# transmitter_with_KS0108_LCD.net
KiCad netlist of a schematic drawn in EAGLE
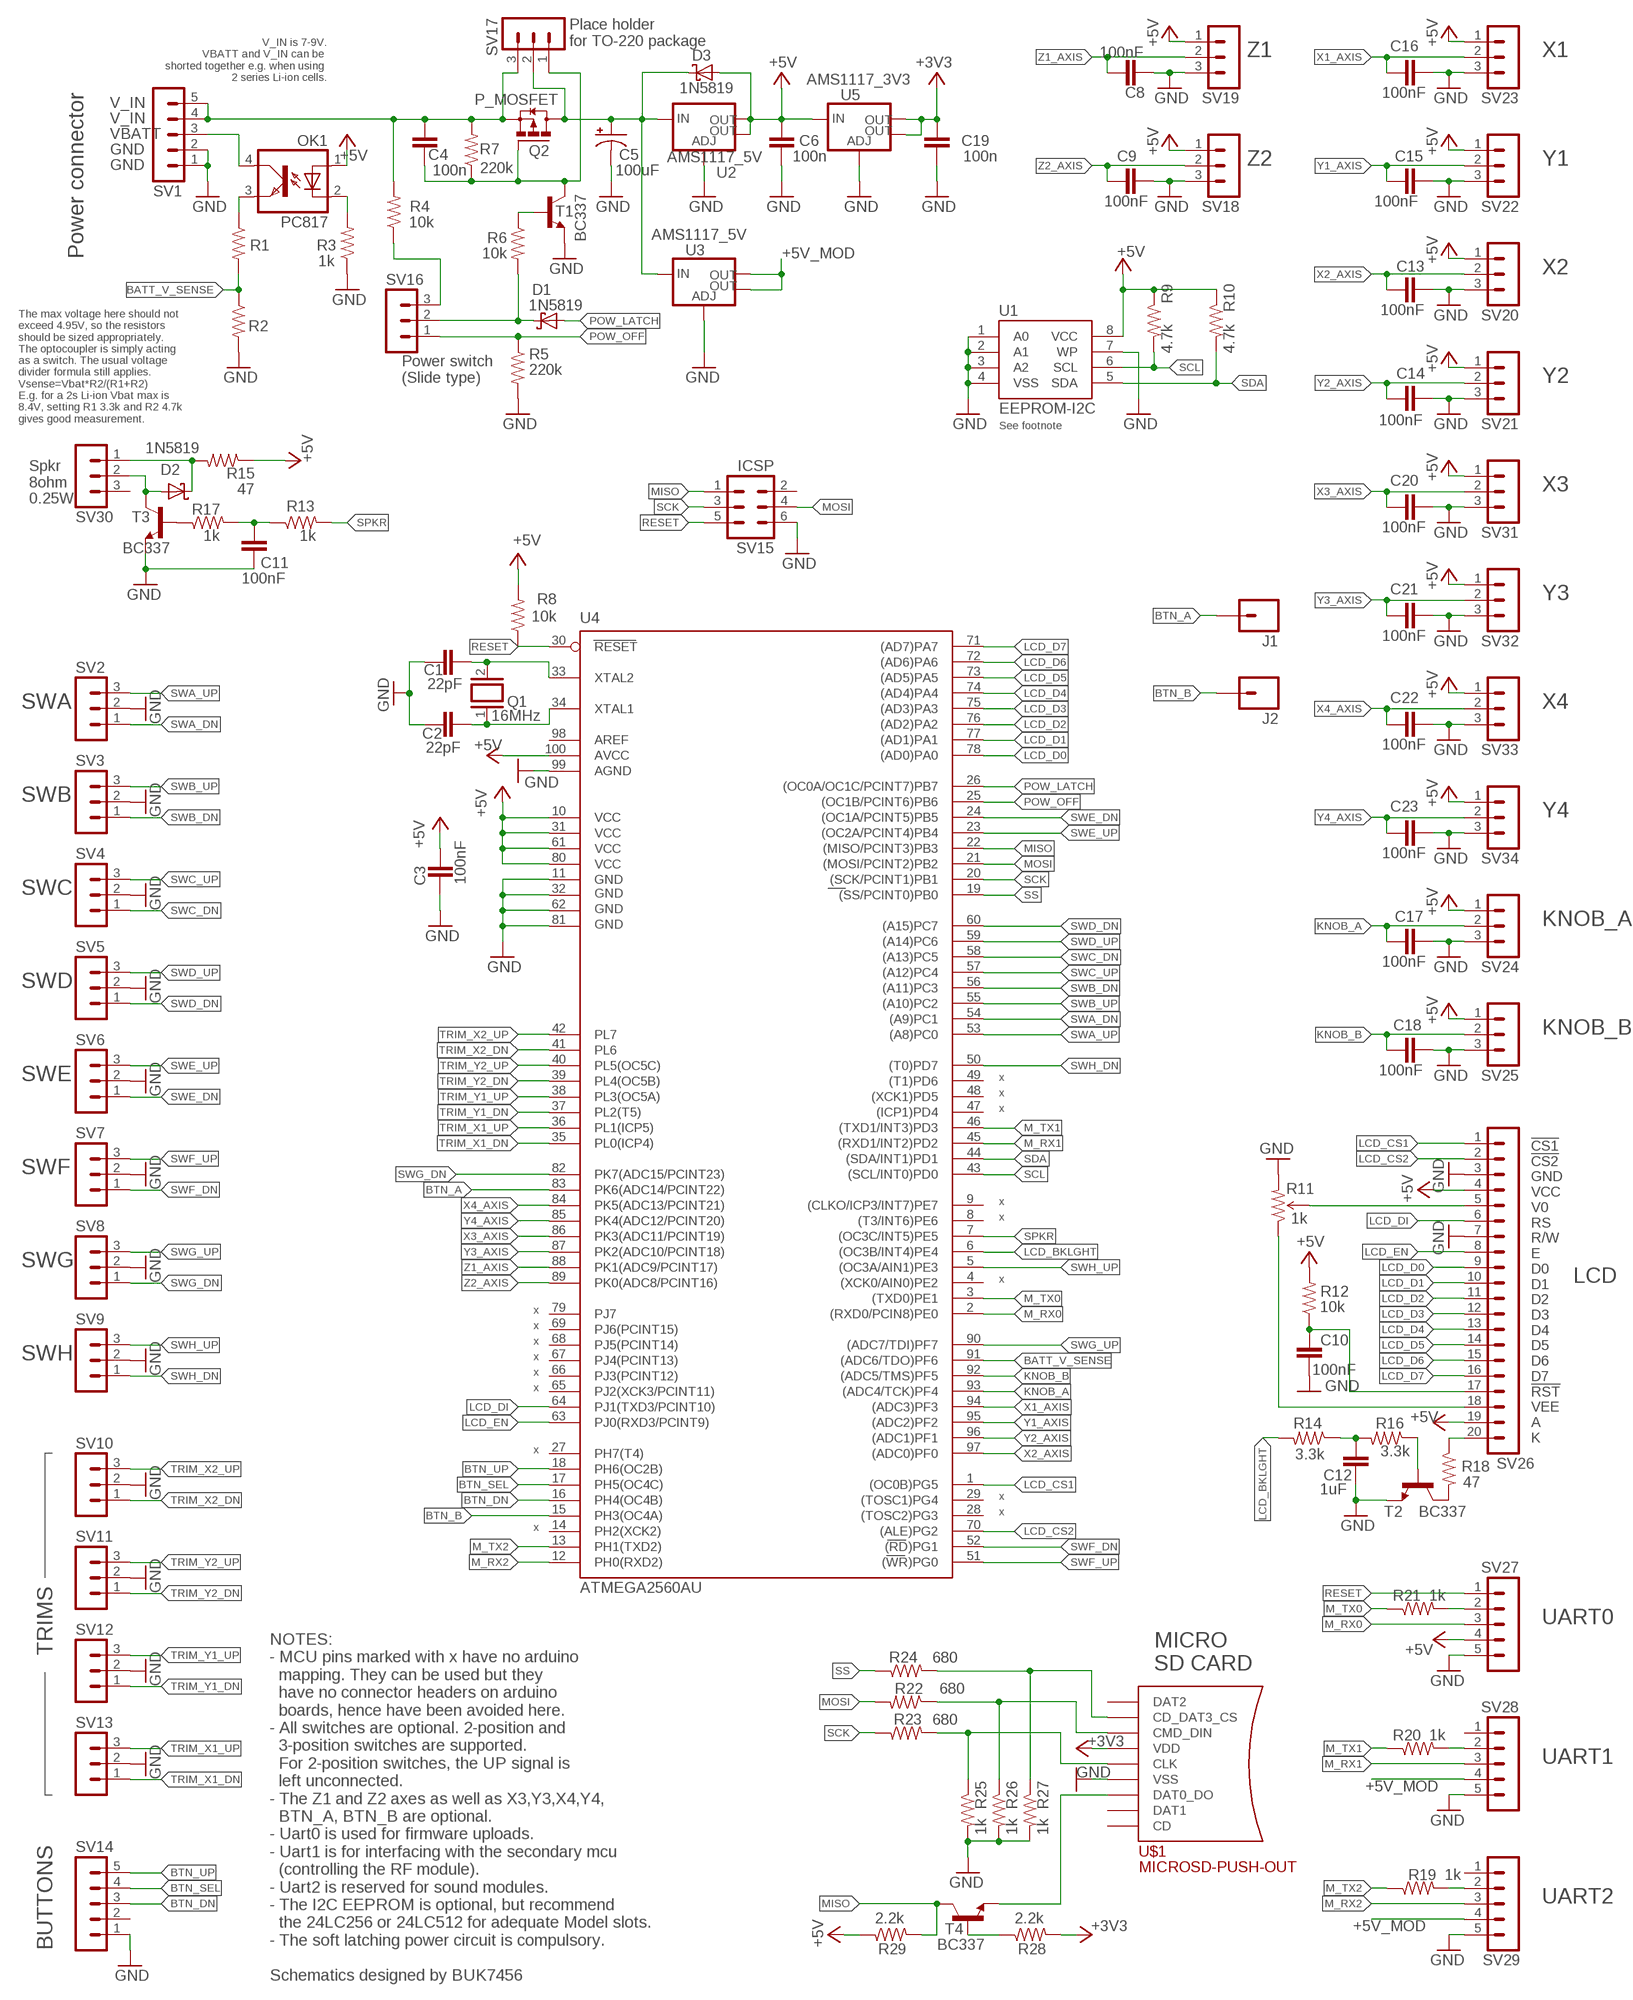
[diagram p0: schematic, sheet 1]

(export (version "E")
  (design (tool "Eeschema 10.0.6"))
  (components
    (comp (ref "C1")
      (value "22pF")
      (footprint "eagle-import:C050-024X044")
      (libsource (lib "eagle-import") (part "C-EU050-024X044"))
    )
    (comp (ref "C2")
      (value "22pF")
      (footprint "eagle-import:C050-024X044")
      (libsource (lib "eagle-import") (part "C-EU050-024X044"))
    )
    (comp (ref "C3")
      (value "100nF")
      (footprint "eagle-import:C050-024X044")
      (libsource (lib "eagle-import") (part "C-EU050-024X044"))
    )
    (comp (ref "C4")
      (value "100n")
      (footprint "eagle-import:C050-024X044")
      (libsource (lib "eagle-import") (part "C-EU050-024X044"))
    )
    (comp (ref "C5")
      (value "100uF")
      (footprint "eagle-import:E2,5-6E")
      (libsource (lib "eagle-import") (part "CPOL-USE2,5-6E"))
    )
    (comp (ref "C6")
      (value "100n")
      (footprint "eagle-import:C050-024X044")
      (libsource (lib "eagle-import") (part "C-EU050-024X044"))
    )
    (comp (ref "C8")
      (value "100nF")
      (footprint "eagle-import:C050-024X044")
      (libsource (lib "eagle-import") (part "C-EU050-024X044"))
    )
    (comp (ref "C9")
      (value "100nF")
      (footprint "eagle-import:C050-024X044")
      (libsource (lib "eagle-import") (part "C-EU050-024X044"))
    )
    (comp (ref "C10")
      (value "100nF")
      (footprint "eagle-import:C050-024X044")
      (libsource (lib "eagle-import") (part "C-EU050-024X044"))
    )
    (comp (ref "C11")
      (value "100nF")
      (footprint "eagle-import:C050-024X044")
      (libsource (lib "eagle-import") (part "C-EU050-024X044"))
    )
    (comp (ref "C12")
      (value "1uF")
      (footprint "eagle-import:C050-024X044")
      (libsource (lib "eagle-import") (part "C-EU050-024X044"))
    )
    (comp (ref "C13")
      (value "100nF")
      (footprint "eagle-import:C050-024X044")
      (libsource (lib "eagle-import") (part "C-EU050-024X044"))
    )
    (comp (ref "C14")
      (value "100nF")
      (footprint "eagle-import:C050-024X044")
      (libsource (lib "eagle-import") (part "C-EU050-024X044"))
    )
    (comp (ref "C15")
      (value "100nF")
      (footprint "eagle-import:C050-024X044")
      (libsource (lib "eagle-import") (part "C-EU050-024X044"))
    )
    (comp (ref "C16")
      (value "100nF")
      (footprint "eagle-import:C050-024X044")
      (libsource (lib "eagle-import") (part "C-EU050-024X044"))
    )
    (comp (ref "C17")
      (value "100nF")
      (footprint "eagle-import:C050-024X044")
      (libsource (lib "eagle-import") (part "C-EU050-024X044"))
    )
    (comp (ref "C18")
      (value "100nF")
      (footprint "eagle-import:C050-024X044")
      (libsource (lib "eagle-import") (part "C-EU050-024X044"))
    )
    (comp (ref "C19")
      (value "100n")
      (footprint "eagle-import:C050-024X044")
      (libsource (lib "eagle-import") (part "C-EU050-024X044"))
    )
    (comp (ref "C20")
      (value "100nF")
      (footprint "eagle-import:C050-024X044")
      (libsource (lib "eagle-import") (part "C-EU050-024X044"))
    )
    (comp (ref "C21")
      (value "100nF")
      (footprint "eagle-import:C050-024X044")
      (libsource (lib "eagle-import") (part "C-EU050-024X044"))
    )
    (comp (ref "C22")
      (value "100nF")
      (footprint "eagle-import:C050-024X044")
      (libsource (lib "eagle-import") (part "C-EU050-024X044"))
    )
    (comp (ref "C23")
      (value "100nF")
      (footprint "eagle-import:C050-024X044")
      (libsource (lib "eagle-import") (part "C-EU050-024X044"))
    )
    (comp (ref "D1")
      (value "1N5819")
      (footprint "eagle-import:DO41-7.6")
      (libsource (lib "eagle-import") (part "1N5817-B"))
    )
    (comp (ref "D2")
      (value "1N5819")
      (footprint "eagle-import:DO41-7.6")
      (libsource (lib "eagle-import") (part "1N5817-B"))
    )
    (comp (ref "D3")
      (value "1N5819")
      (footprint "eagle-import:DO41-7.6")
      (libsource (lib "eagle-import") (part "1N5817-B"))
    )
    (comp (ref "J1")
      (value "M01PTH_LONGPAD")
      (footprint "eagle-import:1X01_LONGPAD")
      (libsource (lib "eagle-import") (part "M01PTH_LONGPAD"))
    )
    (comp (ref "J2")
      (value "M01PTH_LONGPAD")
      (footprint "eagle-import:1X01_LONGPAD")
      (libsource (lib "eagle-import") (part "M01PTH_LONGPAD"))
    )
    (comp (ref "OK1")
      (value "PC817")
      (footprint "eagle-import:DIL04")
      (fields (field (name "MPN") "PC817X4J000F"))
      (libsource (lib "eagle-import") (part "PC817"))
    )
    (comp (ref "Q1")
      (value "16MHz")
      (footprint "eagle-import:QS")
      (libsource (lib "eagle-import") (part "XTAL/S"))
    )
    (comp (ref "Q2")
      (value "P_MOSFET")
      (footprint "eagle-import:SUPER-SOT3")
      (libsource (lib "eagle-import") (part "FDN360P"))
    )
    (comp (ref "R1")
      (value "1k")
      (footprint "eagle-import:0204_5")
      (libsource (lib "eagle-import") (part "R-US_0204/5"))
    )
    (comp (ref "R2")
      (value "1k")
      (footprint "eagle-import:0204_5")
      (libsource (lib "eagle-import") (part "R-US_0204/5"))
    )
    (comp (ref "R3")
      (value "1k")
      (footprint "eagle-import:0204_5")
      (libsource (lib "eagle-import") (part "R-US_0204/5"))
    )
    (comp (ref "R4")
      (value "10k")
      (footprint "eagle-import:0204_5")
      (libsource (lib "eagle-import") (part "R-US_0204/5"))
    )
    (comp (ref "R5")
      (value "220k")
      (footprint "eagle-import:0204_5")
      (libsource (lib "eagle-import") (part "R-US_0204/5"))
    )
    (comp (ref "R6")
      (value "10k")
      (footprint "eagle-import:0204_5")
      (libsource (lib "eagle-import") (part "R-US_0204/5"))
    )
    (comp (ref "R7")
      (value "220k")
      (footprint "eagle-import:0204_5")
      (libsource (lib "eagle-import") (part "R-US_0204/5"))
    )
    (comp (ref "R8")
      (value "10k")
      (footprint "eagle-import:0204_5")
      (libsource (lib "eagle-import") (part "R-US_0204/5"))
    )
    (comp (ref "R9")
      (value "4.7k")
      (footprint "eagle-import:0204_5")
      (libsource (lib "eagle-import") (part "R-US_0204/5"))
    )
    (comp (ref "R10")
      (value "4.7k")
      (footprint "eagle-import:0204_5")
      (libsource (lib "eagle-import") (part "R-US_0204/5"))
    )
    (comp (ref "R11")
      (value "1k")
      (footprint "eagle-import:TRIM_POT_PTH")
      (libsource (lib "eagle-import") (part "TRIMPOTPTH"))
    )
    (comp (ref "R12")
      (value "10k")
      (footprint "eagle-import:0204_5")
      (libsource (lib "eagle-import") (part "resistor_R-US_0204/5"))
    )
    (comp (ref "R13")
      (value "1k")
      (footprint "eagle-import:0204_5")
      (libsource (lib "eagle-import") (part "R-US_0204/5"))
    )
    (comp (ref "R14")
      (value "3.3k")
      (footprint "eagle-import:0204_5")
      (libsource (lib "eagle-import") (part "R-US_0204/5"))
    )
    (comp (ref "R15")
      (value "47")
      (footprint "eagle-import:0204_5")
      (libsource (lib "eagle-import") (part "R-US_0204/5"))
    )
    (comp (ref "R16")
      (value "3.3k")
      (footprint "eagle-import:0204_5")
      (libsource (lib "eagle-import") (part "R-US_0204/5"))
    )
    (comp (ref "R17")
      (value "1k")
      (footprint "eagle-import:0204_5")
      (libsource (lib "eagle-import") (part "R-US_0204/5"))
    )
    (comp (ref "R18")
      (value "47")
      (footprint "eagle-import:0204_5")
      (libsource (lib "eagle-import") (part "R-US_0204/5"))
    )
    (comp (ref "R19")
      (value "1k")
      (footprint "eagle-import:0204_5")
      (libsource (lib "eagle-import") (part "R-US_0204/5"))
    )
    (comp (ref "R20")
      (value "1k")
      (footprint "eagle-import:0204_5")
      (libsource (lib "eagle-import") (part "R-US_0204/5"))
    )
    (comp (ref "R21")
      (value "1k")
      (footprint "eagle-import:0204_5")
      (libsource (lib "eagle-import") (part "R-US_0204/5"))
    )
    (comp (ref "R22")
      (value "680")
      (footprint "eagle-import:0204_5")
      (libsource (lib "eagle-import") (part "R-US_0204/5"))
    )
    (comp (ref "R23")
      (value "680")
      (footprint "eagle-import:0204_5")
      (libsource (lib "eagle-import") (part "R-US_0204/5"))
    )
    (comp (ref "R24")
      (value "680")
      (footprint "eagle-import:0204_5")
      (libsource (lib "eagle-import") (part "R-US_0204/5"))
    )
    (comp (ref "R25")
      (value "1k")
      (footprint "eagle-import:0204_5")
      (libsource (lib "eagle-import") (part "R-US_0204/5"))
    )
    (comp (ref "R26")
      (value "1k")
      (footprint "eagle-import:0204_5")
      (libsource (lib "eagle-import") (part "R-US_0204/5"))
    )
    (comp (ref "R27")
      (value "1k")
      (footprint "eagle-import:0204_5")
      (libsource (lib "eagle-import") (part "R-US_0204/5"))
    )
    (comp (ref "R28")
      (value "2.2k")
      (footprint "eagle-import:0204_5")
      (libsource (lib "eagle-import") (part "R-US_0204/5"))
    )
    (comp (ref "R29")
      (value "2.2k")
      (footprint "eagle-import:0204_5")
      (libsource (lib "eagle-import") (part "R-US_0204/5"))
    )
    (comp (ref "SV1")
      (value "MA05-1")
      (footprint "eagle-import:MA05-1")
      (libsource (lib "eagle-import") (part "MA05-1"))
    )
    (comp (ref "SV2")
      (value "MA03-1")
      (footprint "eagle-import:MA03-1")
      (libsource (lib "eagle-import") (part "MA03-1"))
    )
    (comp (ref "SV3")
      (value "MA03-1")
      (footprint "eagle-import:MA03-1")
      (libsource (lib "eagle-import") (part "MA03-1"))
    )
    (comp (ref "SV4")
      (value "MA03-1")
      (footprint "eagle-import:MA03-1")
      (libsource (lib "eagle-import") (part "MA03-1"))
    )
    (comp (ref "SV5")
      (value "MA03-1")
      (footprint "eagle-import:MA03-1")
      (libsource (lib "eagle-import") (part "MA03-1"))
    )
    (comp (ref "SV6")
      (value "MA03-1")
      (footprint "eagle-import:MA03-1")
      (libsource (lib "eagle-import") (part "MA03-1"))
    )
    (comp (ref "SV7")
      (value "MA03-1")
      (footprint "eagle-import:MA03-1")
      (libsource (lib "eagle-import") (part "MA03-1"))
    )
    (comp (ref "SV8")
      (value "MA03-1")
      (footprint "eagle-import:MA03-1")
      (libsource (lib "eagle-import") (part "MA03-1"))
    )
    (comp (ref "SV9")
      (value "MA03-1")
      (footprint "eagle-import:MA03-1")
      (libsource (lib "eagle-import") (part "MA03-1"))
    )
    (comp (ref "SV10")
      (value "MA03-1")
      (footprint "eagle-import:MA03-1")
      (libsource (lib "eagle-import") (part "MA03-1"))
    )
    (comp (ref "SV11")
      (value "MA03-1")
      (footprint "eagle-import:MA03-1")
      (libsource (lib "eagle-import") (part "MA03-1"))
    )
    (comp (ref "SV12")
      (value "MA03-1")
      (footprint "eagle-import:MA03-1")
      (libsource (lib "eagle-import") (part "MA03-1"))
    )
    (comp (ref "SV13")
      (value "MA03-1")
      (footprint "eagle-import:MA03-1")
      (libsource (lib "eagle-import") (part "MA03-1"))
    )
    (comp (ref "SV14")
      (value "MA05-1")
      (footprint "eagle-import:MA05-1")
      (libsource (lib "eagle-import") (part "MA05-1"))
    )
    (comp (ref "SV15")
      (value "ICSP")
      (footprint "eagle-import:MA03-2")
      (libsource (lib "eagle-import") (part "MA03-2"))
    )
    (comp (ref "SV16")
      (value "MA03-1")
      (footprint "eagle-import:MA03-1")
      (libsource (lib "eagle-import") (part "MA03-1"))
    )
    (comp (ref "SV17")
      (value "MA03-1")
      (footprint "eagle-import:MA03-1")
      (libsource (lib "eagle-import") (part "MA03-1"))
    )
    (comp (ref "SV18")
      (value "MA03-1")
      (footprint "eagle-import:MA03-1")
      (libsource (lib "eagle-import") (part "MA03-1"))
    )
    (comp (ref "SV19")
      (value "MA03-1")
      (footprint "eagle-import:MA03-1")
      (libsource (lib "eagle-import") (part "MA03-1"))
    )
    (comp (ref "SV20")
      (value "MA03-1")
      (footprint "eagle-import:MA03-1")
      (libsource (lib "eagle-import") (part "MA03-1"))
    )
    (comp (ref "SV21")
      (value "MA03-1")
      (footprint "eagle-import:MA03-1")
      (libsource (lib "eagle-import") (part "MA03-1"))
    )
    (comp (ref "SV22")
      (value "MA03-1")
      (footprint "eagle-import:MA03-1")
      (libsource (lib "eagle-import") (part "MA03-1"))
    )
    (comp (ref "SV23")
      (value "MA03-1")
      (footprint "eagle-import:MA03-1")
      (libsource (lib "eagle-import") (part "MA03-1"))
    )
    (comp (ref "SV24")
      (value "MA03-1")
      (footprint "eagle-import:MA03-1")
      (libsource (lib "eagle-import") (part "MA03-1"))
    )
    (comp (ref "SV25")
      (value "MA03-1")
      (footprint "eagle-import:MA03-1")
      (libsource (lib "eagle-import") (part "MA03-1"))
    )
    (comp (ref "SV26")
      (value "MA20-1")
      (footprint "eagle-import:MA20-1")
      (libsource (lib "eagle-import") (part "MA20-1"))
    )
    (comp (ref "SV27")
      (value "MA05-1")
      (footprint "eagle-import:MA05-1")
      (libsource (lib "eagle-import") (part "MA05-1"))
    )
    (comp (ref "SV28")
      (value "MA05-1")
      (footprint "eagle-import:MA05-1")
      (libsource (lib "eagle-import") (part "MA05-1"))
    )
    (comp (ref "SV29")
      (value "MA05-1")
      (footprint "eagle-import:MA05-1")
      (libsource (lib "eagle-import") (part "MA05-1"))
    )
    (comp (ref "SV30")
      (value "MA03-1")
      (footprint "eagle-import:MA03-1")
      (libsource (lib "eagle-import") (part "MA03-1"))
    )
    (comp (ref "SV31")
      (value "MA03-1")
      (footprint "eagle-import:MA03-1")
      (libsource (lib "eagle-import") (part "MA03-1"))
    )
    (comp (ref "SV32")
      (value "MA03-1")
      (footprint "eagle-import:MA03-1")
      (libsource (lib "eagle-import") (part "MA03-1"))
    )
    (comp (ref "SV33")
      (value "MA03-1")
      (footprint "eagle-import:MA03-1")
      (libsource (lib "eagle-import") (part "MA03-1"))
    )
    (comp (ref "SV34")
      (value "MA03-1")
      (footprint "eagle-import:MA03-1")
      (libsource (lib "eagle-import") (part "MA03-1"))
    )
    (comp (ref "T1")
      (value "BC337")
      (footprint "eagle-import:TO92")
      (libsource (lib "eagle-import") (part "BC337"))
    )
    (comp (ref "T2")
      (value "BC337")
      (footprint "eagle-import:TO92")
      (libsource (lib "eagle-import") (part "BC337"))
    )
    (comp (ref "T3")
      (value "BC337")
      (footprint "eagle-import:TO92")
      (libsource (lib "eagle-import") (part "BC337"))
    )
    (comp (ref "T4")
      (value "BC337")
      (footprint "eagle-import:TO92")
      (libsource (lib "eagle-import") (part "BC337"))
    )
    (comp (ref "U$1")
      (value "MICROSD-PUSH-OUT")
      (footprint "eagle-import:MICROSD-PUSH-OUT")
      (libsource (lib "eagle-import") (part "MICROSD-PUSH-OUT"))
    )
    (comp (ref "U1")
      (value "EEPROM-I2C")
      (footprint "eagle-import:SO08-EIAJ")
      (libsource (lib "eagle-import") (part "EEPROM-I2CEIAJ"))
    )
    (comp (ref "U2")
      (value "AMS1117_5V")
      (footprint "eagle-import:SOT223")
      (libsource (lib "eagle-import") (part "V_REG_LM1117SOT223"))
    )
    (comp (ref "U3")
      (value "AMS1117_5V")
      (footprint "eagle-import:SOT223")
      (libsource (lib "eagle-import") (part "V_REG_LM1117SOT223"))
    )
    (comp (ref "U4")
      (value "ATMEGA2560AU")
      (footprint "eagle-import:TQFP100")
      (libsource (lib "eagle-import") (part "ATMEGA2560AU"))
    )
    (comp (ref "U5")
      (value "AMS1117_3V3")
      (footprint "eagle-import:SOT223")
      (libsource (lib "eagle-import") (part "V_REG_LM1117SOT223"))
    )
  )
  (nets
    (net (code "1") (name "+3V3") (class "Default")
      (node (ref "C19") (pin "2") (pinfunction "2_2") (pintype "passive"))
      (node (ref "R28") (pin "2") (pinfunction "2_2") (pintype "passive"))
      (node (ref "U$1") (pin "4") (pinfunction "VDD_4") (pintype "bidirectional"))
      (node (ref "U5") (pin "2") (pinfunction "OUT_2") (pintype "output"))
      (node (ref "U5") (pin "4") (pinfunction "OUT_4") (pintype "output"))
    )
    (net (code "2") (name "+5V") (class "Default")
      (node (ref "C3") (pin "1") (pinfunction "1_1") (pintype "passive"))
      (node (ref "C6") (pin "2") (pinfunction "2_2") (pintype "passive"))
      (node (ref "D3") (pin "A") (pinfunction "A_A") (pintype "passive"))
      (node (ref "OK1") (pin "1") (pinfunction "A_1") (pintype "passive"))
      (node (ref "R10") (pin "1") (pinfunction "1_1") (pintype "passive"))
      (node (ref "R12") (pin "2") (pinfunction "2_2") (pintype "passive"))
      (node (ref "R15") (pin "1") (pinfunction "1_1") (pintype "passive"))
      (node (ref "R29") (pin "1") (pinfunction "1_1") (pintype "passive"))
      (node (ref "R8") (pin "2") (pinfunction "2_2") (pintype "passive"))
      (node (ref "R9") (pin "1") (pinfunction "1_1") (pintype "passive"))
      (node (ref "SV18") (pin "1") (pinfunction "1_1") (pintype "passive"))
      (node (ref "SV19") (pin "1") (pinfunction "1_1") (pintype "passive"))
      (node (ref "SV20") (pin "1") (pinfunction "1_1") (pintype "passive"))
      (node (ref "SV21") (pin "1") (pinfunction "1_1") (pintype "passive"))
      (node (ref "SV22") (pin "1") (pinfunction "1_1") (pintype "passive"))
      (node (ref "SV23") (pin "1") (pinfunction "1_1") (pintype "passive"))
      (node (ref "SV24") (pin "1") (pinfunction "1_1") (pintype "passive"))
      (node (ref "SV25") (pin "1") (pinfunction "1_1") (pintype "passive"))
      (node (ref "SV26") (pin "19") (pinfunction "19_19") (pintype "passive"))
      (node (ref "SV26") (pin "4") (pinfunction "4_4") (pintype "passive"))
      (node (ref "SV27") (pin "4") (pinfunction "4_4") (pintype "passive"))
      (node (ref "SV31") (pin "1") (pinfunction "1_1") (pintype "passive"))
      (node (ref "SV32") (pin "1") (pinfunction "1_1") (pintype "passive"))
      (node (ref "SV33") (pin "1") (pinfunction "1_1") (pintype "passive"))
      (node (ref "SV34") (pin "1") (pinfunction "1_1") (pintype "passive"))
      (node (ref "U1") (pin "8") (pinfunction "VCC_8") (pintype "power_in"))
      (node (ref "U2") (pin "2") (pinfunction "OUT_2") (pintype "output"))
      (node (ref "U2") (pin "4") (pinfunction "OUT_4") (pintype "output"))
      (node (ref "U4") (pin "10") (pinfunction "VCC_10") (pintype "power_in"))
      (node (ref "U4") (pin "100") (pinfunction "AVCC_100") (pintype "power_in"))
      (node (ref "U4") (pin "31") (pinfunction "VCC1_31") (pintype "power_in"))
      (node (ref "U4") (pin "61") (pinfunction "VCC2_61") (pintype "power_in"))
      (node (ref "U4") (pin "80") (pinfunction "VCC3_80") (pintype "power_in"))
      (node (ref "U5") (pin "3") (pinfunction "IN_3") (pintype "input"))
    )
    (net (code "3") (name "/+5V_MOD") (class "Default")
      (node (ref "SV28") (pin "4") (pinfunction "4_4") (pintype "passive"))
      (node (ref "SV29") (pin "4") (pinfunction "4_4") (pintype "passive"))
      (node (ref "U3") (pin "2") (pinfunction "OUT_2") (pintype "output"))
      (node (ref "U3") (pin "4") (pinfunction "OUT_4") (pintype "output"))
    )
    (net (code "4") (name "BATT_V_SENSE") (class "Default")
      (node (ref "R1") (pin "2") (pinfunction "2_2") (pintype "passive"))
      (node (ref "R2") (pin "1") (pinfunction "1_1") (pintype "passive"))
      (node (ref "U4") (pin "91") (pinfunction "(ADC6/TDO)PF6_91") (pintype "bidirectional"))
    )
    (net (code "5") (name "BTN_A") (class "Default")
      (node (ref "J1") (pin "1") (pinfunction "1_1") (pintype "passive"))
      (node (ref "U4") (pin "83") (pinfunction "PK6(ADC14/PCINT22)_83") (pintype "bidirectional"))
    )
    (net (code "6") (name "BTN_B") (class "Default")
      (node (ref "J2") (pin "1") (pinfunction "1_1") (pintype "passive"))
      (node (ref "U4") (pin "15") (pinfunction "PH3(OC4A)_15") (pintype "bidirectional"))
    )
    (net (code "7") (name "BTN_DN") (class "Default")
      (node (ref "SV14") (pin "3") (pinfunction "3_3") (pintype "passive"))
      (node (ref "U4") (pin "16") (pinfunction "PH4(OC4B)_16") (pintype "bidirectional"))
    )
    (net (code "8") (name "BTN_SEL") (class "Default")
      (node (ref "SV14") (pin "4") (pinfunction "4_4") (pintype "passive"))
      (node (ref "U4") (pin "17") (pinfunction "PH5(OC4C)_17") (pintype "bidirectional"))
    )
    (net (code "9") (name "BTN_UP") (class "Default")
      (node (ref "SV14") (pin "5") (pinfunction "5_5") (pintype "passive"))
      (node (ref "U4") (pin "18") (pinfunction "PH6(OC2B)_18") (pintype "bidirectional"))
    )
    (net (code "10") (name "GND") (class "Default")
      (node (ref "C1") (pin "1") (pinfunction "1_1") (pintype "passive"))
      (node (ref "C10") (pin "2") (pinfunction "2_2") (pintype "passive"))
      (node (ref "C11") (pin "2") (pinfunction "2_2") (pintype "passive"))
      (node (ref "C12") (pin "2") (pinfunction "2_2") (pintype "passive"))
      (node (ref "C13") (pin "1") (pinfunction "1_1") (pintype "passive"))
      (node (ref "C14") (pin "1") (pinfunction "1_1") (pintype "passive"))
      (node (ref "C15") (pin "1") (pinfunction "1_1") (pintype "passive"))
      (node (ref "C16") (pin "1") (pinfunction "1_1") (pintype "passive"))
      (node (ref "C17") (pin "1") (pinfunction "1_1") (pintype "passive"))
      (node (ref "C18") (pin "1") (pinfunction "1_1") (pintype "passive"))
      (node (ref "C19") (pin "1") (pinfunction "1_1") (pintype "passive"))
      (node (ref "C2") (pin "1") (pinfunction "1_1") (pintype "passive"))
      (node (ref "C20") (pin "1") (pinfunction "1_1") (pintype "passive"))
      (node (ref "C21") (pin "1") (pinfunction "1_1") (pintype "passive"))
      (node (ref "C22") (pin "1") (pinfunction "1_1") (pintype "passive"))
      (node (ref "C23") (pin "1") (pinfunction "1_1") (pintype "passive"))
      (node (ref "C3") (pin "2") (pinfunction "2_2") (pintype "passive"))
      (node (ref "C5") (pin "-") (pinfunction "-_-") (pintype "passive"))
      (node (ref "C6") (pin "1") (pinfunction "1_1") (pintype "passive"))
      (node (ref "C8") (pin "2") (pinfunction "2_2") (pintype "passive"))
      (node (ref "C9") (pin "1") (pinfunction "1_1") (pintype "passive"))
      (node (ref "R11") (pin "3") (pinfunction "CW_3") (pintype "passive"))
      (node (ref "R2") (pin "2") (pinfunction "2_2") (pintype "passive"))
      (node (ref "R25") (pin "2") (pinfunction "2_2") (pintype "passive"))
      (node (ref "R26") (pin "2") (pinfunction "2_2") (pintype "passive"))
      (node (ref "R27") (pin "2") (pinfunction "2_2") (pintype "passive"))
      (node (ref "R3") (pin "1") (pinfunction "1_1") (pintype "passive"))
      (node (ref "R5") (pin "2") (pinfunction "2_2") (pintype "passive"))
      (node (ref "SV1") (pin "1") (pinfunction "1_1") (pintype "passive"))
      (node (ref "SV1") (pin "2") (pinfunction "2_2") (pintype "passive"))
      (node (ref "SV10") (pin "2") (pinfunction "2_2") (pintype "passive"))
      (node (ref "SV11") (pin "2") (pinfunction "2_2") (pintype "passive"))
      (node (ref "SV12") (pin "2") (pinfunction "2_2") (pintype "passive"))
      (node (ref "SV13") (pin "2") (pinfunction "2_2") (pintype "passive"))
      (node (ref "SV14") (pin "1") (pinfunction "1_1") (pintype "passive"))
      (node (ref "SV15") (pin "6") (pinfunction "6_6") (pintype "passive"))
      (node (ref "SV18") (pin "3") (pinfunction "3_3") (pintype "passive"))
      (node (ref "SV19") (pin "3") (pinfunction "3_3") (pintype "passive"))
      (node (ref "SV2") (pin "2") (pinfunction "2_2") (pintype "passive"))
      (node (ref "SV20") (pin "3") (pinfunction "3_3") (pintype "passive"))
      (node (ref "SV21") (pin "3") (pinfunction "3_3") (pintype "passive"))
      (node (ref "SV22") (pin "3") (pinfunction "3_3") (pintype "passive"))
      (node (ref "SV23") (pin "3") (pinfunction "3_3") (pintype "passive"))
      (node (ref "SV24") (pin "3") (pinfunction "3_3") (pintype "passive"))
      (node (ref "SV25") (pin "3") (pinfunction "3_3") (pintype "passive"))
      (node (ref "SV26") (pin "3") (pinfunction "3_3") (pintype "passive"))
      (node (ref "SV26") (pin "7") (pinfunction "7_7") (pintype "passive"))
      (node (ref "SV27") (pin "5") (pinfunction "5_5") (pintype "passive"))
      (node (ref "SV28") (pin "5") (pinfunction "5_5") (pintype "passive"))
      (node (ref "SV29") (pin "5") (pinfunction "5_5") (pintype "passive"))
      (node (ref "SV3") (pin "2") (pinfunction "2_2") (pintype "passive"))
      (node (ref "SV31") (pin "3") (pinfunction "3_3") (pintype "passive"))
      (node (ref "SV32") (pin "3") (pinfunction "3_3") (pintype "passive"))
      (node (ref "SV33") (pin "3") (pinfunction "3_3") (pintype "passive"))
      (node (ref "SV34") (pin "3") (pinfunction "3_3") (pintype "passive"))
      (node (ref "SV4") (pin "2") (pinfunction "2_2") (pintype "passive"))
      (node (ref "SV5") (pin "2") (pinfunction "2_2") (pintype "passive"))
      (node (ref "SV6") (pin "2") (pinfunction "2_2") (pintype "passive"))
      (node (ref "SV7") (pin "2") (pinfunction "2_2") (pintype "passive"))
      (node (ref "SV8") (pin "2") (pinfunction "2_2") (pintype "passive"))
      (node (ref "SV9") (pin "2") (pinfunction "2_2") (pintype "passive"))
      (node (ref "T1") (pin "1") (pinfunction "E_1") (pintype "passive"))
      (node (ref "T2") (pin "1") (pinfunction "E_1") (pintype "passive"))
      (node (ref "T3") (pin "1") (pinfunction "E_1") (pintype "passive"))
      (node (ref "U$1") (pin "6") (pinfunction "VSS_6") (pintype "bidirectional"))
      (node (ref "U$1") (pin "G1") (pinfunction "VSS_G1") (pintype "bidirectional"))
      (node (ref "U$1") (pin "G2") (pinfunction "VSS_G2") (pintype "bidirectional"))
      (node (ref "U$1") (pin "G3") (pinfunction "VSS_G3") (pintype "bidirectional"))
      (node (ref "U$1") (pin "G4") (pinfunction "VSS_G4") (pintype "bidirectional"))
      (node (ref "U1") (pin "1") (pinfunction "A0_1") (pintype "bidirectional"))
      (node (ref "U1") (pin "2") (pinfunction "A1_2") (pintype "bidirectional"))
      (node (ref "U1") (pin "3") (pinfunction "A2_3") (pintype "bidirectional"))
      (node (ref "U1") (pin "4") (pinfunction "VSS_4") (pintype "power_in"))
      (node (ref "U1") (pin "7") (pinfunction "WP_7") (pintype "bidirectional"))
      (node (ref "U2") (pin "1") (pinfunction "ADJ_1") (pintype "input"))
      (node (ref "U3") (pin "1") (pinfunction "ADJ_1") (pintype "input"))
      (node (ref "U4") (pin "11") (pinfunction "GND_11") (pintype "power_in"))
      (node (ref "U4") (pin "32") (pinfunction "GND1_32") (pintype "power_in"))
      (node (ref "U4") (pin "62") (pinfunction "GND2_62") (pintype "power_in"))
      (node (ref "U4") (pin "81") (pinfunction "GND3_81") (pintype "power_in"))
      (node (ref "U4") (pin "99") (pinfunction "AGND_99") (pintype "power_in"))
      (node (ref "U5") (pin "1") (pinfunction "ADJ_1") (pintype "input"))
    )
    (net (code "11") (name "KNOB_A") (class "Default")
      (node (ref "C17") (pin "2") (pinfunction "2_2") (pintype "passive"))
      (node (ref "SV24") (pin "2") (pinfunction "2_2") (pintype "passive"))
      (node (ref "U4") (pin "93") (pinfunction "(ADC4/TCK)PF4_93") (pintype "bidirectional"))
    )
    (net (code "12") (name "KNOB_B") (class "Default")
      (node (ref "C18") (pin "2") (pinfunction "2_2") (pintype "passive"))
      (node (ref "SV25") (pin "2") (pinfunction "2_2") (pintype "passive"))
      (node (ref "U4") (pin "92") (pinfunction "(ADC5/TMS)PF5_92") (pintype "bidirectional"))
    )
    (net (code "13") (name "LCD_BKLGHT") (class "Default")
      (node (ref "R14") (pin "2") (pinfunction "2_2") (pintype "passive"))
      (node (ref "U4") (pin "6") (pinfunction "(OC3B/INT4)PE4_6") (pintype "bidirectional"))
    )
    (net (code "14") (name "LCD_CS1") (class "Default")
      (node (ref "SV26") (pin "1") (pinfunction "1_1") (pintype "passive"))
      (node (ref "U4") (pin "1") (pinfunction "(OC0B)PG5_1") (pintype "bidirectional"))
    )
    (net (code "15") (name "LCD_CS2") (class "Default")
      (node (ref "SV26") (pin "2") (pinfunction "2_2") (pintype "passive"))
      (node (ref "U4") (pin "70") (pinfunction "(ALE)PG2_70") (pintype "bidirectional"))
    )
    (net (code "16") (name "LCD_D0") (class "Default")
      (node (ref "SV26") (pin "9") (pinfunction "9_9") (pintype "passive"))
      (node (ref "U4") (pin "78") (pinfunction "(AD0)PA0_78") (pintype "bidirectional"))
    )
    (net (code "17") (name "LCD_D1") (class "Default")
      (node (ref "SV26") (pin "10") (pinfunction "10_10") (pintype "passive"))
      (node (ref "U4") (pin "77") (pinfunction "(AD1)PA1_77") (pintype "bidirectional"))
    )
    (net (code "18") (name "LCD_D2") (class "Default")
      (node (ref "SV26") (pin "11") (pinfunction "11_11") (pintype "passive"))
      (node (ref "U4") (pin "76") (pinfunction "(AD2)PA2_76") (pintype "bidirectional"))
    )
    (net (code "19") (name "LCD_D3") (class "Default")
      (node (ref "SV26") (pin "12") (pinfunction "12_12") (pintype "passive"))
      (node (ref "U4") (pin "75") (pinfunction "(AD3)PA3_75") (pintype "bidirectional"))
    )
    (net (code "20") (name "LCD_D4") (class "Default")
      (node (ref "SV26") (pin "13") (pinfunction "13_13") (pintype "passive"))
      (node (ref "U4") (pin "74") (pinfunction "(AD4)PA4_74") (pintype "bidirectional"))
    )
    (net (code "21") (name "LCD_D5") (class "Default")
      (node (ref "SV26") (pin "14") (pinfunction "14_14") (pintype "passive"))
      (node (ref "U4") (pin "73") (pinfunction "(AD5)PA5_73") (pintype "bidirectional"))
    )
    (net (code "22") (name "LCD_D6") (class "Default")
      (node (ref "SV26") (pin "15") (pinfunction "15_15") (pintype "passive"))
      (node (ref "U4") (pin "72") (pinfunction "(AD6)PA6_72") (pintype "bidirectional"))
    )
    (net (code "23") (name "LCD_D7") (class "Default")
      (node (ref "SV26") (pin "16") (pinfunction "16_16") (pintype "passive"))
      (node (ref "U4") (pin "71") (pinfunction "(AD7)PA7_71") (pintype "bidirectional"))
    )
    (net (code "24") (name "LCD_DI") (class "Default")
      (node (ref "SV26") (pin "6") (pinfunction "6_6") (pintype "passive"))
      (node (ref "U4") (pin "64") (pinfunction "PJ1(TXD3/PCINT10)_64") (pintype "bidirectional"))
    )
    (net (code "25") (name "LCD_EN") (class "Default")
      (node (ref "SV26") (pin "8") (pinfunction "8_8") (pintype "passive"))
      (node (ref "U4") (pin "63") (pinfunction "PJ0(RXD3/PCINT9)_63") (pintype "bidirectional"))
    )
    (net (code "26") (name "MISO") (class "Default")
      (node (ref "R29") (pin "2") (pinfunction "2_2") (pintype "passive"))
      (node (ref "SV15") (pin "1") (pinfunction "1_1") (pintype "passive"))
      (node (ref "T4") (pin "3") (pinfunction "C_3") (pintype "passive"))
      (node (ref "U4") (pin "22") (pinfunction "(MISO/PCINT3)PB3_22") (pintype "bidirectional"))
    )
    (net (code "27") (name "MOSI") (class "Default")
      (node (ref "R22") (pin "2") (pinfunction "2_2") (pintype "passive"))
      (node (ref "SV15") (pin "4") (pinfunction "4_4") (pintype "passive"))
      (node (ref "U4") (pin "21") (pinfunction "(MOSI/PCINT2)PB2_21") (pintype "bidirectional"))
    )
    (net (code "28") (name "M_RX0") (class "Default")
      (node (ref "SV27") (pin "3") (pinfunction "3_3") (pintype "passive"))
      (node (ref "U4") (pin "2") (pinfunction "(RXD0/PCIN8)PE0_2") (pintype "bidirectional"))
    )
    (net (code "29") (name "M_RX1") (class "Default")
      (node (ref "SV28") (pin "3") (pinfunction "3_3") (pintype "passive"))
      (node (ref "U4") (pin "45") (pinfunction "(RXD1/INT2)PD2_45") (pintype "bidirectional"))
    )
    (net (code "30") (name "M_RX2") (class "Default")
      (node (ref "SV29") (pin "3") (pinfunction "3_3") (pintype "passive"))
      (node (ref "U4") (pin "12") (pinfunction "PH0(RXD2)_12") (pintype "bidirectional"))
    )
    (net (code "31") (name "M_TX0") (class "Default")
      (node (ref "R21") (pin "1") (pinfunction "1_1") (pintype "passive"))
      (node (ref "U4") (pin "3") (pinfunction "(TXD0)PE1_3") (pintype "bidirectional"))
    )
    (net (code "32") (name "M_TX1") (class "Default")
      (node (ref "R20") (pin "1") (pinfunction "1_1") (pintype "passive"))
      (node (ref "U4") (pin "46") (pinfunction "(TXD1/INT3)PD3_46") (pintype "bidirectional"))
    )
    (net (code "33") (name "M_TX2") (class "Default")
      (node (ref "R19") (pin "1") (pinfunction "1_1") (pintype "passive"))
      (node (ref "U4") (pin "13") (pinfunction "PH1(TXD2)_13") (pintype "bidirectional"))
    )
    (net (code "34") (name "Net-(C10-Pad1)") (class "Default")
      (node (ref "C10") (pin "1") (pinfunction "1_1") (pintype "passive"))
      (node (ref "R12") (pin "1") (pinfunction "1_1") (pintype "passive"))
      (node (ref "SV26") (pin "17") (pinfunction "17_17") (pintype "passive"))
    )
    (net (code "35") (name "Net-(C11-Pad1)") (class "Default")
      (node (ref "C11") (pin "1") (pinfunction "1_1") (pintype "passive"))
      (node (ref "R13") (pin "1") (pinfunction "1_1") (pintype "passive"))
      (node (ref "R17") (pin "2") (pinfunction "2_2") (pintype "passive"))
    )
    (net (code "36") (name "Net-(C12-Pad1)") (class "Default")
      (node (ref "C12") (pin "1") (pinfunction "1_1") (pintype "passive"))
      (node (ref "R14") (pin "1") (pinfunction "1_1") (pintype "passive"))
      (node (ref "R16") (pin "2") (pinfunction "2_2") (pintype "passive"))
    )
    (net (code "37") (name "Net-(D1-PadC)") (class "Default")
      (node (ref "D1") (pin "C") (pinfunction "C_C") (pintype "passive"))
      (node (ref "R6") (pin "2") (pinfunction "2_2") (pintype "passive"))
      (node (ref "SV16") (pin "2") (pinfunction "2_2") (pintype "passive"))
    )
    (net (code "38") (name "Net-(D2-PadC)") (class "Default")
      (node (ref "D2") (pin "C") (pinfunction "C_C") (pintype "passive"))
      (node (ref "R15") (pin "2") (pinfunction "2_2") (pintype "passive"))
      (node (ref "SV30") (pin "1") (pinfunction "1_1") (pintype "passive"))
    )
    (net (code "39") (name "Net-(OK1-C)") (class "Default")
      (node (ref "OK1") (pin "2") (pinfunction "C_2") (pintype "passive"))
      (node (ref "R3") (pin "2") (pinfunction "2_2") (pintype "passive"))
    )
    (net (code "40") (name "Net-(OK1-COL)") (class "Default")
      (node (ref "OK1") (pin "4") (pinfunction "COL_4") (pintype "passive"))
      (node (ref "SV1") (pin "3") (pinfunction "3_3") (pintype "passive"))
    )
    (net (code "41") (name "Net-(OK1-EMIT)") (class "Default")
      (node (ref "OK1") (pin "3") (pinfunction "EMIT_3") (pintype "passive"))
      (node (ref "R1") (pin "1") (pinfunction "1_1") (pintype "passive"))
    )
    (net (code "42") (name "Net-(Q2-D)") (class "Default")
      (node (ref "C5") (pin "+") (pinfunction "+_+") (pintype "passive"))
      (node (ref "D3") (pin "C") (pinfunction "C_C") (pintype "passive"))
      (node (ref "Q2") (pin "3") (pinfunction "D_3") (pintype "passive"))
      (node (ref "SV17") (pin "2") (pinfunction "2_2") (pintype "passive"))
      (node (ref "U2") (pin "3") (pinfunction "IN_3") (pintype "input"))
      (node (ref "U3") (pin "3") (pinfunction "IN_3") (pintype "input"))
    )
    (net (code "43") (name "Net-(Q2-G)") (class "Default")
      (node (ref "C4") (pin "1") (pinfunction "1_1") (pintype "passive"))
      (node (ref "Q2") (pin "1") (pinfunction "G_1") (pintype "passive"))
      (node (ref "R7") (pin "1") (pinfunction "1_1") (pintype "passive"))
      (node (ref "SV17") (pin "1") (pinfunction "1_1") (pintype "passive"))
      (node (ref "T1") (pin "3") (pinfunction "C_3") (pintype "passive"))
    )
    (net (code "44") (name "Net-(Q2-S)") (class "Default")
      (node (ref "C4") (pin "2") (pinfunction "2_2") (pintype "passive"))
      (node (ref "Q2") (pin "2") (pinfunction "S_2") (pintype "passive"))
      (node (ref "R4") (pin "2") (pinfunction "2_2") (pintype "passive"))
      (node (ref "R7") (pin "2") (pinfunction "2_2") (pintype "passive"))
      (node (ref "SV1") (pin "4") (pinfunction "4_4") (pintype "passive"))
      (node (ref "SV1") (pin "5") (pinfunction "5_5") (pintype "passive"))
      (node (ref "SV17") (pin "3") (pinfunction "3_3") (pintype "passive"))
    )
    (net (code "45") (name "Net-(R4-Pad1)") (class "Default")
      (node (ref "R4") (pin "1") (pinfunction "1_1") (pintype "passive"))
      (node (ref "SV16") (pin "3") (pinfunction "3_3") (pintype "passive"))
    )
    (net (code "46") (name "Net-(R11-CCW)") (class "Default")
      (node (ref "R11") (pin "1") (pinfunction "CCW_1") (pintype "passive"))
      (node (ref "SV26") (pin "18") (pinfunction "18_18") (pintype "passive"))
    )
    (net (code "47") (name "Net-(R11-WIPER)") (class "Default")
      (node (ref "R11") (pin "2") (pinfunction "WIPER_2") (pintype "passive"))
      (node (ref "SV26") (pin "5") (pinfunction "5_5") (pintype "passive"))
    )
    (net (code "48") (name "Net-(R18-Pad1)") (class "Default")
      (node (ref "R18") (pin "1") (pinfunction "1_1") (pintype "passive"))
      (node (ref "SV26") (pin "20") (pinfunction "20_20") (pintype "passive"))
    )
    (net (code "49") (name "Net-(R19-Pad2)") (class "Default")
      (node (ref "R19") (pin "2") (pinfunction "2_2") (pintype "passive"))
      (node (ref "SV29") (pin "2") (pinfunction "2_2") (pintype "passive"))
    )
    (net (code "50") (name "Net-(R20-Pad2)") (class "Default")
      (node (ref "R20") (pin "2") (pinfunction "2_2") (pintype "passive"))
      (node (ref "SV28") (pin "2") (pinfunction "2_2") (pintype "passive"))
    )
    (net (code "51") (name "Net-(R21-Pad2)") (class "Default")
      (node (ref "R21") (pin "2") (pinfunction "2_2") (pintype "passive"))
      (node (ref "SV27") (pin "2") (pinfunction "2_2") (pintype "passive"))
    )
    (net (code "52") (name "Net-(T1-B)") (class "Default")
      (node (ref "R6") (pin "1") (pinfunction "1_1") (pintype "passive"))
      (node (ref "T1") (pin "2") (pinfunction "B_2") (pintype "passive"))
    )
    (net (code "53") (name "Net-(T2-B)") (class "Default")
      (node (ref "R16") (pin "1") (pinfunction "1_1") (pintype "passive"))
      (node (ref "T2") (pin "2") (pinfunction "B_2") (pintype "passive"))
    )
    (net (code "54") (name "Net-(T2-C)") (class "Default")
      (node (ref "R18") (pin "2") (pinfunction "2_2") (pintype "passive"))
      (node (ref "T2") (pin "3") (pinfunction "C_3") (pintype "passive"))
    )
    (net (code "55") (name "Net-(T3-B)") (class "Default")
      (node (ref "R17") (pin "1") (pinfunction "1_1") (pintype "passive"))
      (node (ref "T3") (pin "2") (pinfunction "B_2") (pintype "passive"))
    )
    (net (code "56") (name "Net-(T3-C)") (class "Default")
      (node (ref "D2") (pin "A") (pinfunction "A_A") (pintype "passive"))
      (node (ref "SV30") (pin "2") (pinfunction "2_2") (pintype "passive"))
      (node (ref "T3") (pin "3") (pinfunction "C_3") (pintype "passive"))
    )
    (net (code "57") (name "Net-(T4-B)") (class "Default")
      (node (ref "R28") (pin "1") (pinfunction "1_1") (pintype "passive"))
      (node (ref "T4") (pin "2") (pinfunction "B_2") (pintype "passive"))
    )
    (net (code "58") (name "Net-(T4-E)") (class "Default")
      (node (ref "T4") (pin "1") (pinfunction "E_1") (pintype "passive"))
      (node (ref "U$1") (pin "7") (pinfunction "DAT0_DO_7") (pintype "bidirectional"))
    )
    (net (code "59") (name "Net-(U$1-CD_DAT3_CS)") (class "Default")
      (node (ref "R24") (pin "2") (pinfunction "2_2") (pintype "passive"))
      (node (ref "R27") (pin "1") (pinfunction "1_1") (pintype "passive"))
      (node (ref "U$1") (pin "2") (pinfunction "CD_DAT3_CS_2") (pintype "bidirectional"))
    )
    (net (code "60") (name "Net-(U$1-CLK)") (class "Default")
      (node (ref "R23") (pin "2") (pinfunction "2_2") (pintype "passive"))
      (node (ref "R25") (pin "1") (pinfunction "1_1") (pintype "passive"))
      (node (ref "U$1") (pin "5") (pinfunction "CLK_5") (pintype "bidirectional"))
    )
    (net (code "61") (name "Net-(U$1-CMD_DIN)") (class "Default")
      (node (ref "R22") (pin "1") (pinfunction "1_1") (pintype "passive"))
      (node (ref "R26") (pin "1") (pinfunction "1_1") (pintype "passive"))
      (node (ref "U$1") (pin "3") (pinfunction "CMD_DIN_3") (pintype "bidirectional"))
    )
    (net (code "62") (name "Net-(U4-XTAL1)") (class "Default")
      (node (ref "C2") (pin "2") (pinfunction "2_2") (pintype "passive"))
      (node (ref "Q1") (pin "1") (pinfunction "1_1") (pintype "passive"))
      (node (ref "U4") (pin "34") (pinfunction "XTAL1_34") (pintype "input"))
    )
    (net (code "63") (name "Net-(U4-XTAL2)") (class "Default")
      (node (ref "C1") (pin "2") (pinfunction "2_2") (pintype "passive"))
      (node (ref "Q1") (pin "2") (pinfunction "2_2") (pintype "passive"))
      (node (ref "U4") (pin "33") (pinfunction "XTAL2_33") (pintype "output"))
    )
    (net (code "64") (name "POW_LATCH") (class "Default")
      (node (ref "D1") (pin "A") (pinfunction "A_A") (pintype "passive"))
      (node (ref "U4") (pin "26") (pinfunction "(OC0A/OC1C/PCINT7)PB7_26") (pintype "bidirectional"))
    )
    (net (code "65") (name "POW_OFF") (class "Default")
      (node (ref "R5") (pin "1") (pinfunction "1_1") (pintype "passive"))
      (node (ref "SV16") (pin "1") (pinfunction "1_1") (pintype "passive"))
      (node (ref "U4") (pin "25") (pinfunction "(OC1B/PCINT6)PB6_25") (pintype "bidirectional"))
    )
    (net (code "66") (name "RESET") (class "Default")
      (node (ref "R8") (pin "1") (pinfunction "1_1") (pintype "passive"))
      (node (ref "SV15") (pin "5") (pinfunction "5_5") (pintype "passive"))
      (node (ref "SV27") (pin "1") (pinfunction "1_1") (pintype "passive"))
      (node (ref "U4") (pin "30") (pinfunction "RESET_30") (pintype "input"))
    )
    (net (code "67") (name "SCK") (class "Default")
      (node (ref "R23") (pin "1") (pinfunction "1_1") (pintype "passive"))
      (node (ref "SV15") (pin "3") (pinfunction "3_3") (pintype "passive"))
      (node (ref "U4") (pin "20") (pinfunction "(SCK/PCINT1)PB1_20") (pintype "bidirectional"))
    )
    (net (code "68") (name "SCL") (class "Default")
      (node (ref "R9") (pin "2") (pinfunction "2_2") (pintype "passive"))
      (node (ref "U1") (pin "6") (pinfunction "SCL_6") (pintype "bidirectional"))
      (node (ref "U4") (pin "43") (pinfunction "(SCL/INT0)PD0_43") (pintype "bidirectional"))
    )
    (net (code "69") (name "SDA") (class "Default")
      (node (ref "R10") (pin "2") (pinfunction "2_2") (pintype "passive"))
      (node (ref "U1") (pin "5") (pinfunction "SDA_5") (pintype "bidirectional"))
      (node (ref "U4") (pin "44") (pinfunction "(SDA/INT1)PD1_44") (pintype "bidirectional"))
    )
    (net (code "70") (name "SPKR") (class "Default")
      (node (ref "R13") (pin "2") (pinfunction "2_2") (pintype "passive"))
      (node (ref "U4") (pin "7") (pinfunction "(OC3C/INT5)PE5_7") (pintype "bidirectional"))
    )
    (net (code "71") (name "SS") (class "Default")
      (node (ref "R24") (pin "1") (pinfunction "1_1") (pintype "passive"))
      (node (ref "U4") (pin "19") (pinfunction "(SS/PCINT0)PB0_19") (pintype "bidirectional"))
    )
    (net (code "72") (name "SWA_DN") (class "Default")
      (node (ref "SV2") (pin "1") (pinfunction "1_1") (pintype "passive"))
      (node (ref "U4") (pin "54") (pinfunction "(A9)PC1_54") (pintype "bidirectional"))
    )
    (net (code "73") (name "SWA_UP") (class "Default")
      (node (ref "SV2") (pin "3") (pinfunction "3_3") (pintype "passive"))
      (node (ref "U4") (pin "53") (pinfunction "(A8)PC0_53") (pintype "bidirectional"))
    )
    (net (code "74") (name "SWB_DN") (class "Default")
      (node (ref "SV3") (pin "1") (pinfunction "1_1") (pintype "passive"))
      (node (ref "U4") (pin "56") (pinfunction "(A11)PC3_56") (pintype "bidirectional"))
    )
    (net (code "75") (name "SWB_UP") (class "Default")
      (node (ref "SV3") (pin "3") (pinfunction "3_3") (pintype "passive"))
      (node (ref "U4") (pin "55") (pinfunction "(A10)PC2_55") (pintype "bidirectional"))
    )
    (net (code "76") (name "SWC_DN") (class "Default")
      (node (ref "SV4") (pin "1") (pinfunction "1_1") (pintype "passive"))
      (node (ref "U4") (pin "58") (pinfunction "(A13)PC5_58") (pintype "bidirectional"))
    )
    (net (code "77") (name "SWC_UP") (class "Default")
      (node (ref "SV4") (pin "3") (pinfunction "3_3") (pintype "passive"))
      (node (ref "U4") (pin "57") (pinfunction "(A12)PC4_57") (pintype "bidirectional"))
    )
    (net (code "78") (name "SWD_DN") (class "Default")
      (node (ref "SV5") (pin "1") (pinfunction "1_1") (pintype "passive"))
      (node (ref "U4") (pin "60") (pinfunction "(A15)PC7_60") (pintype "bidirectional"))
    )
    (net (code "79") (name "SWD_UP") (class "Default")
      (node (ref "SV5") (pin "3") (pinfunction "3_3") (pintype "passive"))
      (node (ref "U4") (pin "59") (pinfunction "(A14)PC6_59") (pintype "bidirectional"))
    )
    (net (code "80") (name "SWE_DN") (class "Default")
      (node (ref "SV6") (pin "1") (pinfunction "1_1") (pintype "passive"))
      (node (ref "U4") (pin "24") (pinfunction "(OC1A/PCINT5)PB5_24") (pintype "bidirectional"))
    )
    (net (code "81") (name "SWE_UP") (class "Default")
      (node (ref "SV6") (pin "3") (pinfunction "3_3") (pintype "passive"))
      (node (ref "U4") (pin "23") (pinfunction "(OC2A/PCINT4)PB4_23") (pintype "bidirectional"))
    )
    (net (code "82") (name "SWF_DN") (class "Default")
      (node (ref "SV7") (pin "1") (pinfunction "1_1") (pintype "passive"))
      (node (ref "U4") (pin "52") (pinfunction "(RD)PG1_52") (pintype "bidirectional"))
    )
    (net (code "83") (name "SWF_UP") (class "Default")
      (node (ref "SV7") (pin "3") (pinfunction "3_3") (pintype "passive"))
      (node (ref "U4") (pin "51") (pinfunction "(WR)PG0_51") (pintype "bidirectional"))
    )
    (net (code "84") (name "SWG_DN") (class "Default")
      (node (ref "SV8") (pin "1") (pinfunction "1_1") (pintype "passive"))
      (node (ref "U4") (pin "82") (pinfunction "PK7(ADC15/PCINT23)_82") (pintype "bidirectional"))
    )
    (net (code "85") (name "SWG_UP") (class "Default")
      (node (ref "SV8") (pin "3") (pinfunction "3_3") (pintype "passive"))
      (node (ref "U4") (pin "90") (pinfunction "(ADC7/TDI)PF7_90") (pintype "bidirectional"))
    )
    (net (code "86") (name "SWH_DN") (class "Default")
      (node (ref "SV9") (pin "1") (pinfunction "1_1") (pintype "passive"))
      (node (ref "U4") (pin "50") (pinfunction "(T0)PD7_50") (pintype "bidirectional"))
    )
    (net (code "87") (name "SWH_UP") (class "Default")
      (node (ref "SV9") (pin "3") (pinfunction "3_3") (pintype "passive"))
      (node (ref "U4") (pin "5") (pinfunction "(OC3A/AIN1)PE3_5") (pintype "bidirectional"))
    )
    (net (code "88") (name "TRIM_X1_DN") (class "Default")
      (node (ref "SV13") (pin "1") (pinfunction "1_1") (pintype "passive"))
      (node (ref "U4") (pin "35") (pinfunction "PL0(ICP4)_35") (pintype "bidirectional"))
    )
    (net (code "89") (name "TRIM_X1_UP") (class "Default")
      (node (ref "SV13") (pin "3") (pinfunction "3_3") (pintype "passive"))
      (node (ref "U4") (pin "36") (pinfunction "PL1(ICP5)_36") (pintype "bidirectional"))
    )
    (net (code "90") (name "TRIM_X2_DN") (class "Default")
      (node (ref "SV10") (pin "1") (pinfunction "1_1") (pintype "passive"))
      (node (ref "U4") (pin "41") (pinfunction "PL6_41") (pintype "bidirectional"))
    )
    (net (code "91") (name "TRIM_X2_UP") (class "Default")
      (node (ref "SV10") (pin "3") (pinfunction "3_3") (pintype "passive"))
      (node (ref "U4") (pin "42") (pinfunction "PL7_42") (pintype "bidirectional"))
    )
    (net (code "92") (name "TRIM_Y1_DN") (class "Default")
      (node (ref "SV12") (pin "1") (pinfunction "1_1") (pintype "passive"))
      (node (ref "U4") (pin "37") (pinfunction "PL2(T5)_37") (pintype "bidirectional"))
    )
    (net (code "93") (name "TRIM_Y1_UP") (class "Default")
      (node (ref "SV12") (pin "3") (pinfunction "3_3") (pintype "passive"))
      (node (ref "U4") (pin "38") (pinfunction "PL3(OC5A)_38") (pintype "bidirectional"))
    )
    (net (code "94") (name "TRIM_Y2_DN") (class "Default")
      (node (ref "SV11") (pin "1") (pinfunction "1_1") (pintype "passive"))
      (node (ref "U4") (pin "39") (pinfunction "PL4(OC5B)_39") (pintype "bidirectional"))
    )
    (net (code "95") (name "TRIM_Y2_UP") (class "Default")
      (node (ref "SV11") (pin "3") (pinfunction "3_3") (pintype "passive"))
      (node (ref "U4") (pin "40") (pinfunction "PL5(OC5C)_40") (pintype "bidirectional"))
    )
    (net (code "96") (name "X1_AXIS") (class "Default")
      (node (ref "C16") (pin "2") (pinfunction "2_2") (pintype "passive"))
      (node (ref "SV23") (pin "2") (pinfunction "2_2") (pintype "passive"))
      (node (ref "U4") (pin "94") (pinfunction "(ADC3)PF3_94") (pintype "bidirectional"))
    )
    (net (code "97") (name "X2_AXIS") (class "Default")
      (node (ref "C13") (pin "2") (pinfunction "2_2") (pintype "passive"))
      (node (ref "SV20") (pin "2") (pinfunction "2_2") (pintype "passive"))
      (node (ref "U4") (pin "97") (pinfunction "(ADC0)PF0_97") (pintype "bidirectional"))
    )
    (net (code "98") (name "X3_AXIS") (class "Default")
      (node (ref "C20") (pin "2") (pinfunction "2_2") (pintype "passive"))
      (node (ref "SV31") (pin "2") (pinfunction "2_2") (pintype "passive"))
      (node (ref "U4") (pin "86") (pinfunction "PK3(ADC11/PCINT19)_86") (pintype "bidirectional"))
    )
    (net (code "99") (name "X4_AXIS") (class "Default")
      (node (ref "C22") (pin "2") (pinfunction "2_2") (pintype "passive"))
      (node (ref "SV33") (pin "2") (pinfunction "2_2") (pintype "passive"))
      (node (ref "U4") (pin "84") (pinfunction "PK5(ADC13/PCINT21)_84") (pintype "bidirectional"))
    )
    (net (code "100") (name "Y1_AXIS") (class "Default")
      (node (ref "C15") (pin "2") (pinfunction "2_2") (pintype "passive"))
      (node (ref "SV22") (pin "2") (pinfunction "2_2") (pintype "passive"))
      (node (ref "U4") (pin "95") (pinfunction "(ADC2)PF2_95") (pintype "bidirectional"))
    )
    (net (code "101") (name "Y2_AXIS") (class "Default")
      (node (ref "C14") (pin "2") (pinfunction "2_2") (pintype "passive"))
      (node (ref "SV21") (pin "2") (pinfunction "2_2") (pintype "passive"))
      (node (ref "U4") (pin "96") (pinfunction "(ADC1)PF1_96") (pintype "bidirectional"))
    )
    (net (code "102") (name "Y3_AXIS") (class "Default")
      (node (ref "C21") (pin "2") (pinfunction "2_2") (pintype "passive"))
      (node (ref "SV32") (pin "2") (pinfunction "2_2") (pintype "passive"))
      (node (ref "U4") (pin "87") (pinfunction "PK2(ADC10/PCINT18)_87") (pintype "bidirectional"))
    )
    (net (code "103") (name "Y4_AXIS") (class "Default")
      (node (ref "C23") (pin "2") (pinfunction "2_2") (pintype "passive"))
      (node (ref "SV34") (pin "2") (pinfunction "2_2") (pintype "passive"))
      (node (ref "U4") (pin "85") (pinfunction "PK4(ADC12/PCINT20)_85") (pintype "bidirectional"))
    )
    (net (code "104") (name "Z1_AXIS") (class "Default")
      (node (ref "C8") (pin "1") (pinfunction "1_1") (pintype "passive"))
      (node (ref "SV19") (pin "2") (pinfunction "2_2") (pintype "passive"))
      (node (ref "U4") (pin "88") (pinfunction "PK1(ADC9/PCINT17)_88") (pintype "bidirectional"))
    )
    (net (code "105") (name "Z2_AXIS") (class "Default")
      (node (ref "C9") (pin "2") (pinfunction "2_2") (pintype "passive"))
      (node (ref "SV18") (pin "2") (pinfunction "2_2") (pintype "passive"))
      (node (ref "U4") (pin "89") (pinfunction "PK0(ADC8/PCINT16)_89") (pintype "bidirectional"))
    )
    (net (code "106") (name "unconnected-(SV14-Pad2)") (class "Default")
      (node (ref "SV14") (pin "2") (pinfunction "2_2") (pintype "passive"))
    )
    (net (code "107") (name "unconnected-(SV15-Pad2)") (class "Default")
      (node (ref "SV15") (pin "2") (pinfunction "2_2") (pintype "passive"))
    )
    (net (code "108") (name "unconnected-(SV28-Pad1)") (class "Default")
      (node (ref "SV28") (pin "1") (pinfunction "1_1") (pintype "passive"))
    )
    (net (code "109") (name "unconnected-(SV29-Pad1)") (class "Default")
      (node (ref "SV29") (pin "1") (pinfunction "1_1") (pintype "passive"))
    )
    (net (code "110") (name "unconnected-(SV30-Pad3)") (class "Default")
      (node (ref "SV30") (pin "3") (pinfunction "3_3") (pintype "passive"))
    )
    (net (code "111") (name "unconnected-(U$1-DAT1-Pad8)") (class "Default")
      (node (ref "U$1") (pin "8") (pinfunction "DAT1_8") (pintype "bidirectional"))
    )
    (net (code "112") (name "unconnected-(U$1-DAT2-Pad1)") (class "Default")
      (node (ref "U$1") (pin "1") (pinfunction "DAT2_1") (pintype "bidirectional"))
    )
    (net (code "113") (name "unconnected-(U$1-PadCD)") (class "Default")
      (node (ref "U$1") (pin "CD") (pinfunction "CD_CD") (pintype "bidirectional"))
    )
    (net (code "114") (name "unconnected-(U4-(CLKO{slash}ICP3{slash}INT7)PE7-Pad9)") (class "Default")
      (node (ref "U4") (pin "9") (pinfunction "(CLKO/ICP3/INT7)PE7_9") (pintype "bidirectional"))
    )
    (net (code "115") (name "unconnected-(U4-(ICP1)PD4-Pad47)") (class "Default")
      (node (ref "U4") (pin "47") (pinfunction "(ICP1)PD4_47") (pintype "bidirectional"))
    )
    (net (code "116") (name "unconnected-(U4-(T1)PD6-Pad49)") (class "Default")
      (node (ref "U4") (pin "49") (pinfunction "(T1)PD6_49") (pintype "bidirectional"))
    )
    (net (code "117") (name "unconnected-(U4-(T3{slash}INT6)PE6-Pad8)") (class "Default")
      (node (ref "U4") (pin "8") (pinfunction "(T3/INT6)PE6_8") (pintype "bidirectional"))
    )
    (net (code "118") (name "unconnected-(U4-(TOSC1)PG4-Pad29)") (class "Default")
      (node (ref "U4") (pin "29") (pinfunction "(TOSC1)PG4_29") (pintype "bidirectional"))
    )
    (net (code "119") (name "unconnected-(U4-(TOSC2)PG3-Pad28)") (class "Default")
      (node (ref "U4") (pin "28") (pinfunction "(TOSC2)PG3_28") (pintype "bidirectional"))
    )
    (net (code "120") (name "unconnected-(U4-(XCK0{slash}AIN0)PE2-Pad4)") (class "Default")
      (node (ref "U4") (pin "4") (pinfunction "(XCK0/AIN0)PE2_4") (pintype "bidirectional"))
    )
    (net (code "121") (name "unconnected-(U4-(XCK1)PD5-Pad48)") (class "Default")
      (node (ref "U4") (pin "48") (pinfunction "(XCK1)PD5_48") (pintype "bidirectional"))
    )
    (net (code "122") (name "unconnected-(U4-AREF-Pad98)") (class "Default")
      (node (ref "U4") (pin "98") (pinfunction "AREF_98") (pintype "bidirectional"))
    )
    (net (code "123") (name "unconnected-(U4-PH2(XCK2)-Pad14)") (class "Default")
      (node (ref "U4") (pin "14") (pinfunction "PH2(XCK2)_14") (pintype "bidirectional"))
    )
    (net (code "124") (name "unconnected-(U4-PH7(T4)-Pad27)") (class "Default")
      (node (ref "U4") (pin "27") (pinfunction "PH7(T4)_27") (pintype "bidirectional"))
    )
    (net (code "125") (name "unconnected-(U4-PJ2(XCK3{slash}PCINT11)-Pad65)") (class "Default")
      (node (ref "U4") (pin "65") (pinfunction "PJ2(XCK3/PCINT11)_65") (pintype "bidirectional"))
    )
    (net (code "126") (name "unconnected-(U4-PJ3(PCINT12)-Pad66)") (class "Default")
      (node (ref "U4") (pin "66") (pinfunction "PJ3(PCINT12)_66") (pintype "bidirectional"))
    )
    (net (code "127") (name "unconnected-(U4-PJ4(PCINT13)-Pad67)") (class "Default")
      (node (ref "U4") (pin "67") (pinfunction "PJ4(PCINT13)_67") (pintype "bidirectional"))
    )
    (net (code "128") (name "unconnected-(U4-PJ5(PCINT14)-Pad68)") (class "Default")
      (node (ref "U4") (pin "68") (pinfunction "PJ5(PCINT14)_68") (pintype "bidirectional"))
    )
    (net (code "129") (name "unconnected-(U4-PJ6(PCINT15)-Pad69)") (class "Default")
      (node (ref "U4") (pin "69") (pinfunction "PJ6(PCINT15)_69") (pintype "bidirectional"))
    )
    (net (code "130") (name "unconnected-(U4-PJ7-Pad79)") (class "Default")
      (node (ref "U4") (pin "79") (pinfunction "PJ7_79") (pintype "bidirectional"))
    )
  )
)
